# 02A-005_Input_Switch.net
KiCad netlist of a schematic drawn in EAGLE
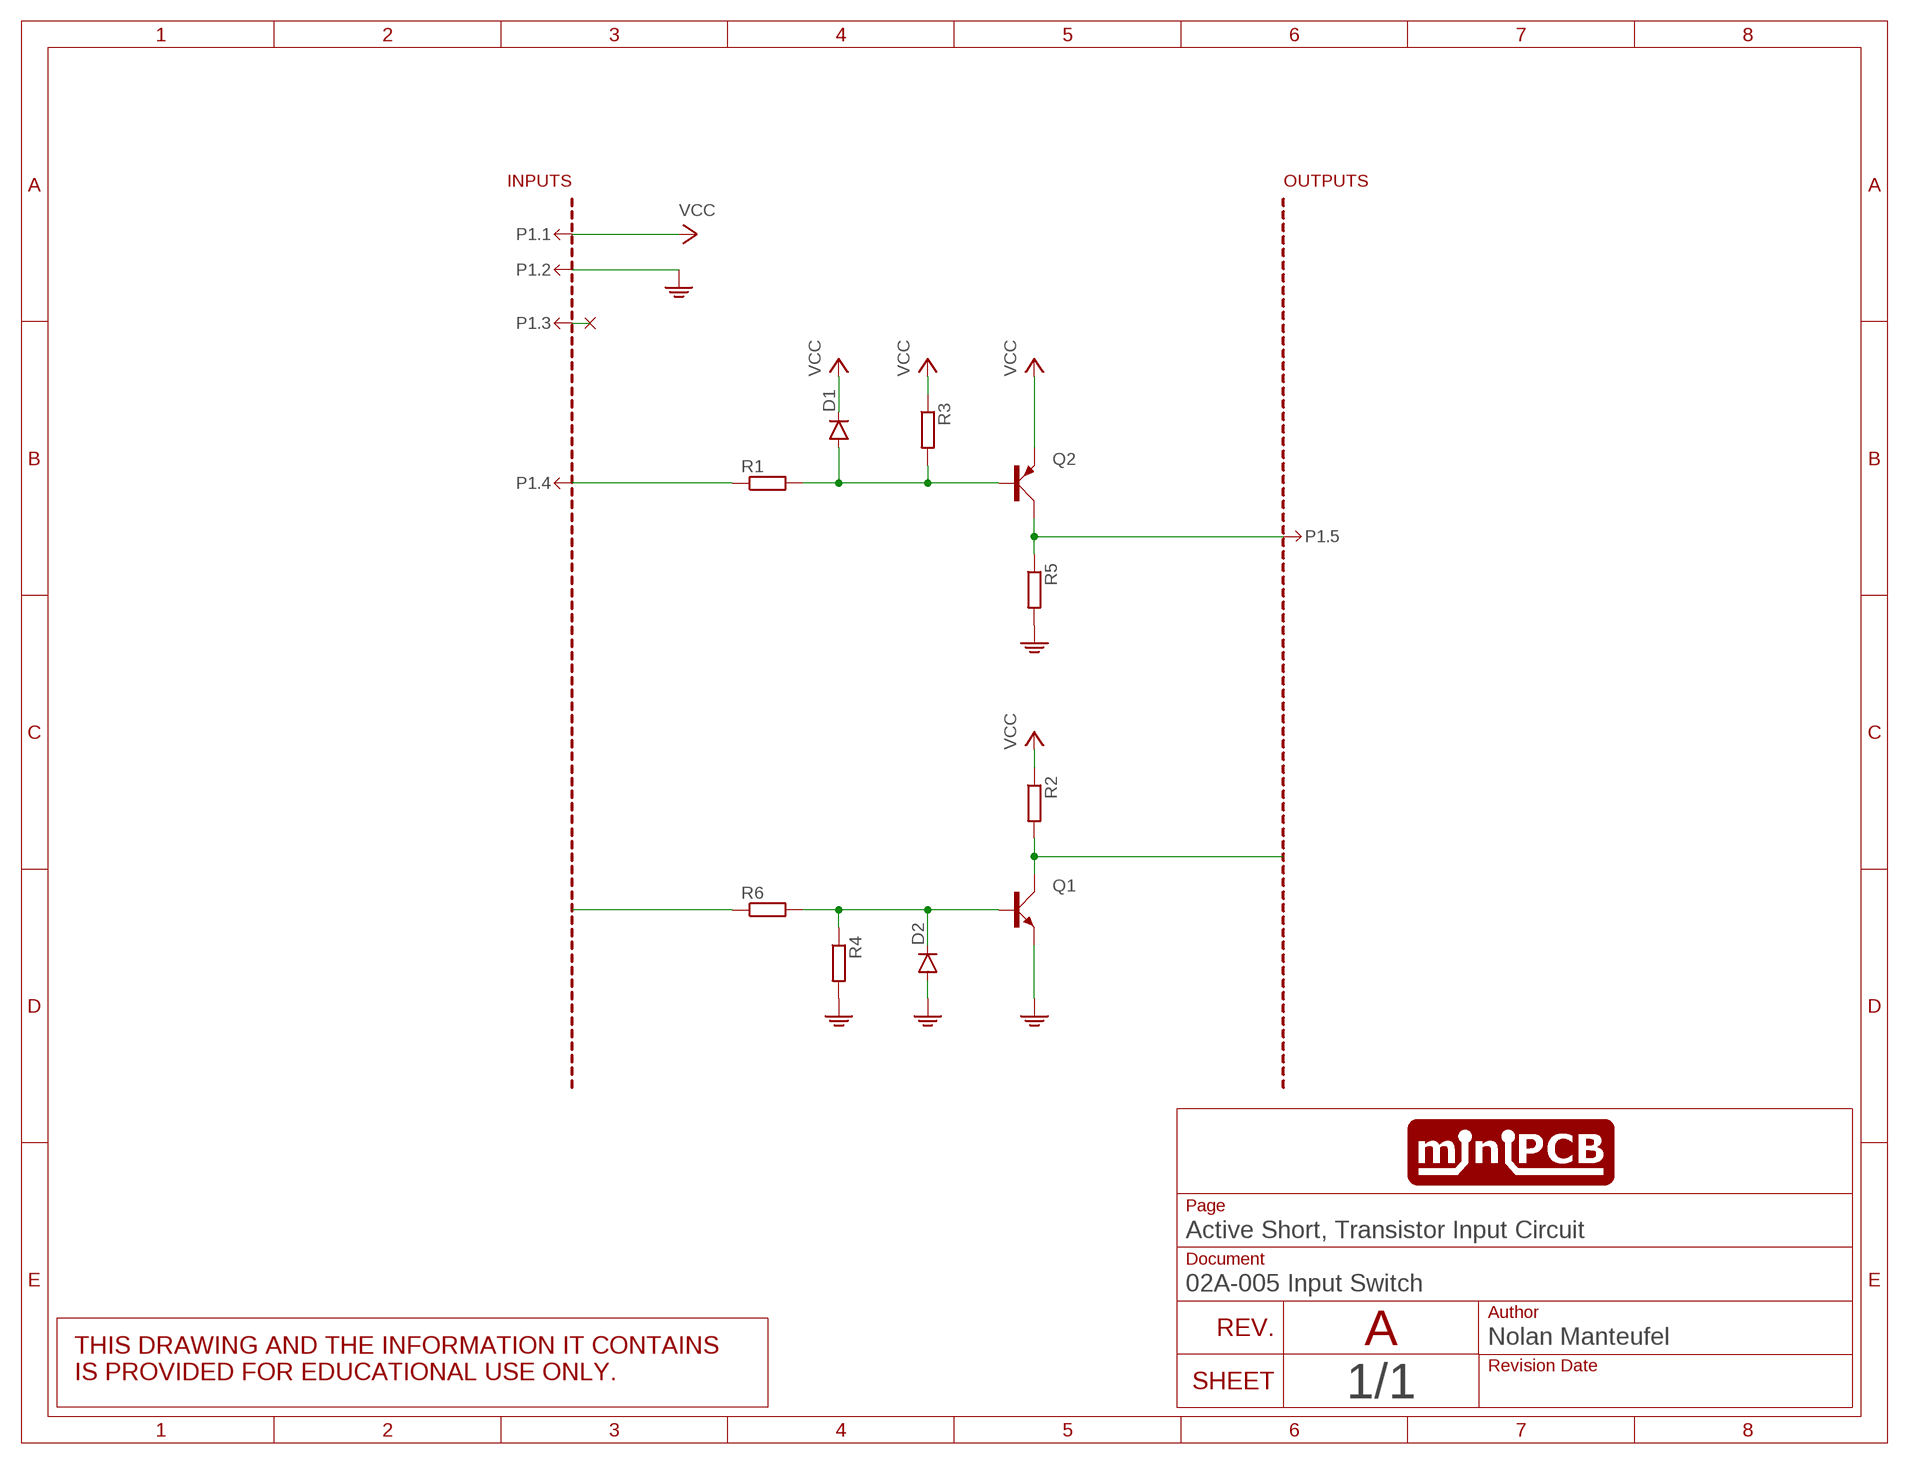
[diagram p0: schematic, sheet 1]

(export (version "E")
  (design (tool "Eeschema 10.0.6"))
  (components
    (comp (ref "D1")
      (value "DIODE-SOD80C")
      (footprint "eagle-import:SOD80C")
      (libsource (lib "eagle-import") (part "DIODE-SOD80C"))
    )
    (comp (ref "D2")
      (value "DIODE-SOD80C")
      (footprint "eagle-import:SOD80C")
      (libsource (lib "eagle-import") (part "DIODE-SOD80C"))
    )
    (comp (ref "P1.")
      (value "MINIPCB_4INCH")
      (footprint "eagle-import:PCB_5")
      (libsource (lib "eagle-import") (part "MINIPCB_4INCH"))
    )
    (comp (ref "Q1")
      (value "BJT_NPNBEC")
      (footprint "eagle-import:SOT23")
      (libsource (lib "eagle-import") (part "BJT_NPNBEC"))
    )
    (comp (ref "Q2")
      (value "BJT_PNPBEC")
      (footprint "eagle-import:SOT23")
      (libsource (lib "eagle-import") (part "BJT_PNPBEC"))
    )
    (comp (ref "R1")
      (value "R-EU_R0805")
      (footprint "eagle-import:R0805")
      (libsource (lib "eagle-import") (part "R-EU_R0805"))
    )
    (comp (ref "R2")
      (value "R-EU_R0805")
      (footprint "eagle-import:R0805")
      (libsource (lib "eagle-import") (part "R-EU_R0805"))
    )
    (comp (ref "R3")
      (value "R-EU_R0805")
      (footprint "eagle-import:R0805")
      (libsource (lib "eagle-import") (part "R-EU_R0805"))
    )
    (comp (ref "R4")
      (value "R-EU_R0805")
      (footprint "eagle-import:R0805")
      (libsource (lib "eagle-import") (part "R-EU_R0805"))
    )
    (comp (ref "R5")
      (value "R-EU_R0805")
      (footprint "eagle-import:R0805")
      (libsource (lib "eagle-import") (part "R-EU_R0805"))
    )
    (comp (ref "R6")
      (value "R-EU_R0805")
      (footprint "eagle-import:R0805")
      (libsource (lib "eagle-import") (part "R-EU_R0805"))
    )
  )
  (nets
    (net (code "1") (name "GND") (class "Default")
      (node (ref "D2") (pin "A") (pinfunction "A_A") (pintype "passive"))
      (node (ref "P1.") (pin "1") (pinfunction "1_1") (pintype "bidirectional"))
      (node (ref "Q1") (pin "2") (pinfunction "E_2") (pintype "passive"))
      (node (ref "R4") (pin "2") (pinfunction "2_2") (pintype "passive"))
      (node (ref "R5") (pin "2") (pinfunction "2_2") (pintype "passive"))
    )
    (net (code "2") (name "Net-(P1.D-1)") (class "Default")
      (node (ref "P1.") (pin "4") (pinfunction "1_4") (pintype "bidirectional"))
      (node (ref "R1") (pin "1") (pinfunction "1_1") (pintype "passive"))
    )
    (net (code "3") (name "Net-(P1.H-1)") (class "Default")
      (node (ref "P1.") (pin "5") (pinfunction "1_5") (pintype "bidirectional"))
      (node (ref "Q2") (pin "3") (pinfunction "C_3") (pintype "passive"))
      (node (ref "R5") (pin "1") (pinfunction "1_1") (pintype "passive"))
    )
    (net (code "4") (name "Net-(Q1-B)") (class "Default")
      (node (ref "D2") (pin "C") (pinfunction "C_C") (pintype "passive"))
      (node (ref "Q1") (pin "1") (pinfunction "B_1") (pintype "passive"))
      (node (ref "R4") (pin "1") (pinfunction "1_1") (pintype "passive"))
      (node (ref "R6") (pin "2") (pinfunction "2_2") (pintype "passive"))
    )
    (net (code "5") (name "Net-(Q1-C)") (class "Default")
      (node (ref "Q1") (pin "3") (pinfunction "C_3") (pintype "passive"))
      (node (ref "R2") (pin "2") (pinfunction "2_2") (pintype "passive"))
    )
    (net (code "6") (name "Net-(Q2-B)") (class "Default")
      (node (ref "D1") (pin "A") (pinfunction "A_A") (pintype "passive"))
      (node (ref "Q2") (pin "1") (pinfunction "B_1") (pintype "passive"))
      (node (ref "R1") (pin "2") (pinfunction "2_2") (pintype "passive"))
      (node (ref "R3") (pin "2") (pinfunction "2_2") (pintype "passive"))
    )
    (net (code "7") (name "VCC") (class "Default")
      (node (ref "D1") (pin "C") (pinfunction "C_C") (pintype "passive"))
      (node (ref "P1.") (pin "2") (pinfunction "1_2") (pintype "bidirectional"))
      (node (ref "Q2") (pin "2") (pinfunction "E_2") (pintype "passive"))
      (node (ref "R2") (pin "1") (pinfunction "1_1") (pintype "passive"))
      (node (ref "R3") (pin "1") (pinfunction "1_1") (pintype "passive"))
    )
    (net (code "8") (name "unconnected-(P1.C-1-Pad3)") (class "Default")
      (node (ref "P1.") (pin "3") (pinfunction "1_3") (pintype "bidirectional"))
    )
    (net (code "9") (name "unconnected-(R6-Pad1)") (class "Default")
      (node (ref "R6") (pin "1") (pinfunction "1_1") (pintype "passive"))
    )
  )
)
